# 8255_pio_1_4.net
KiCad netlist of a schematic drawn in EAGLE
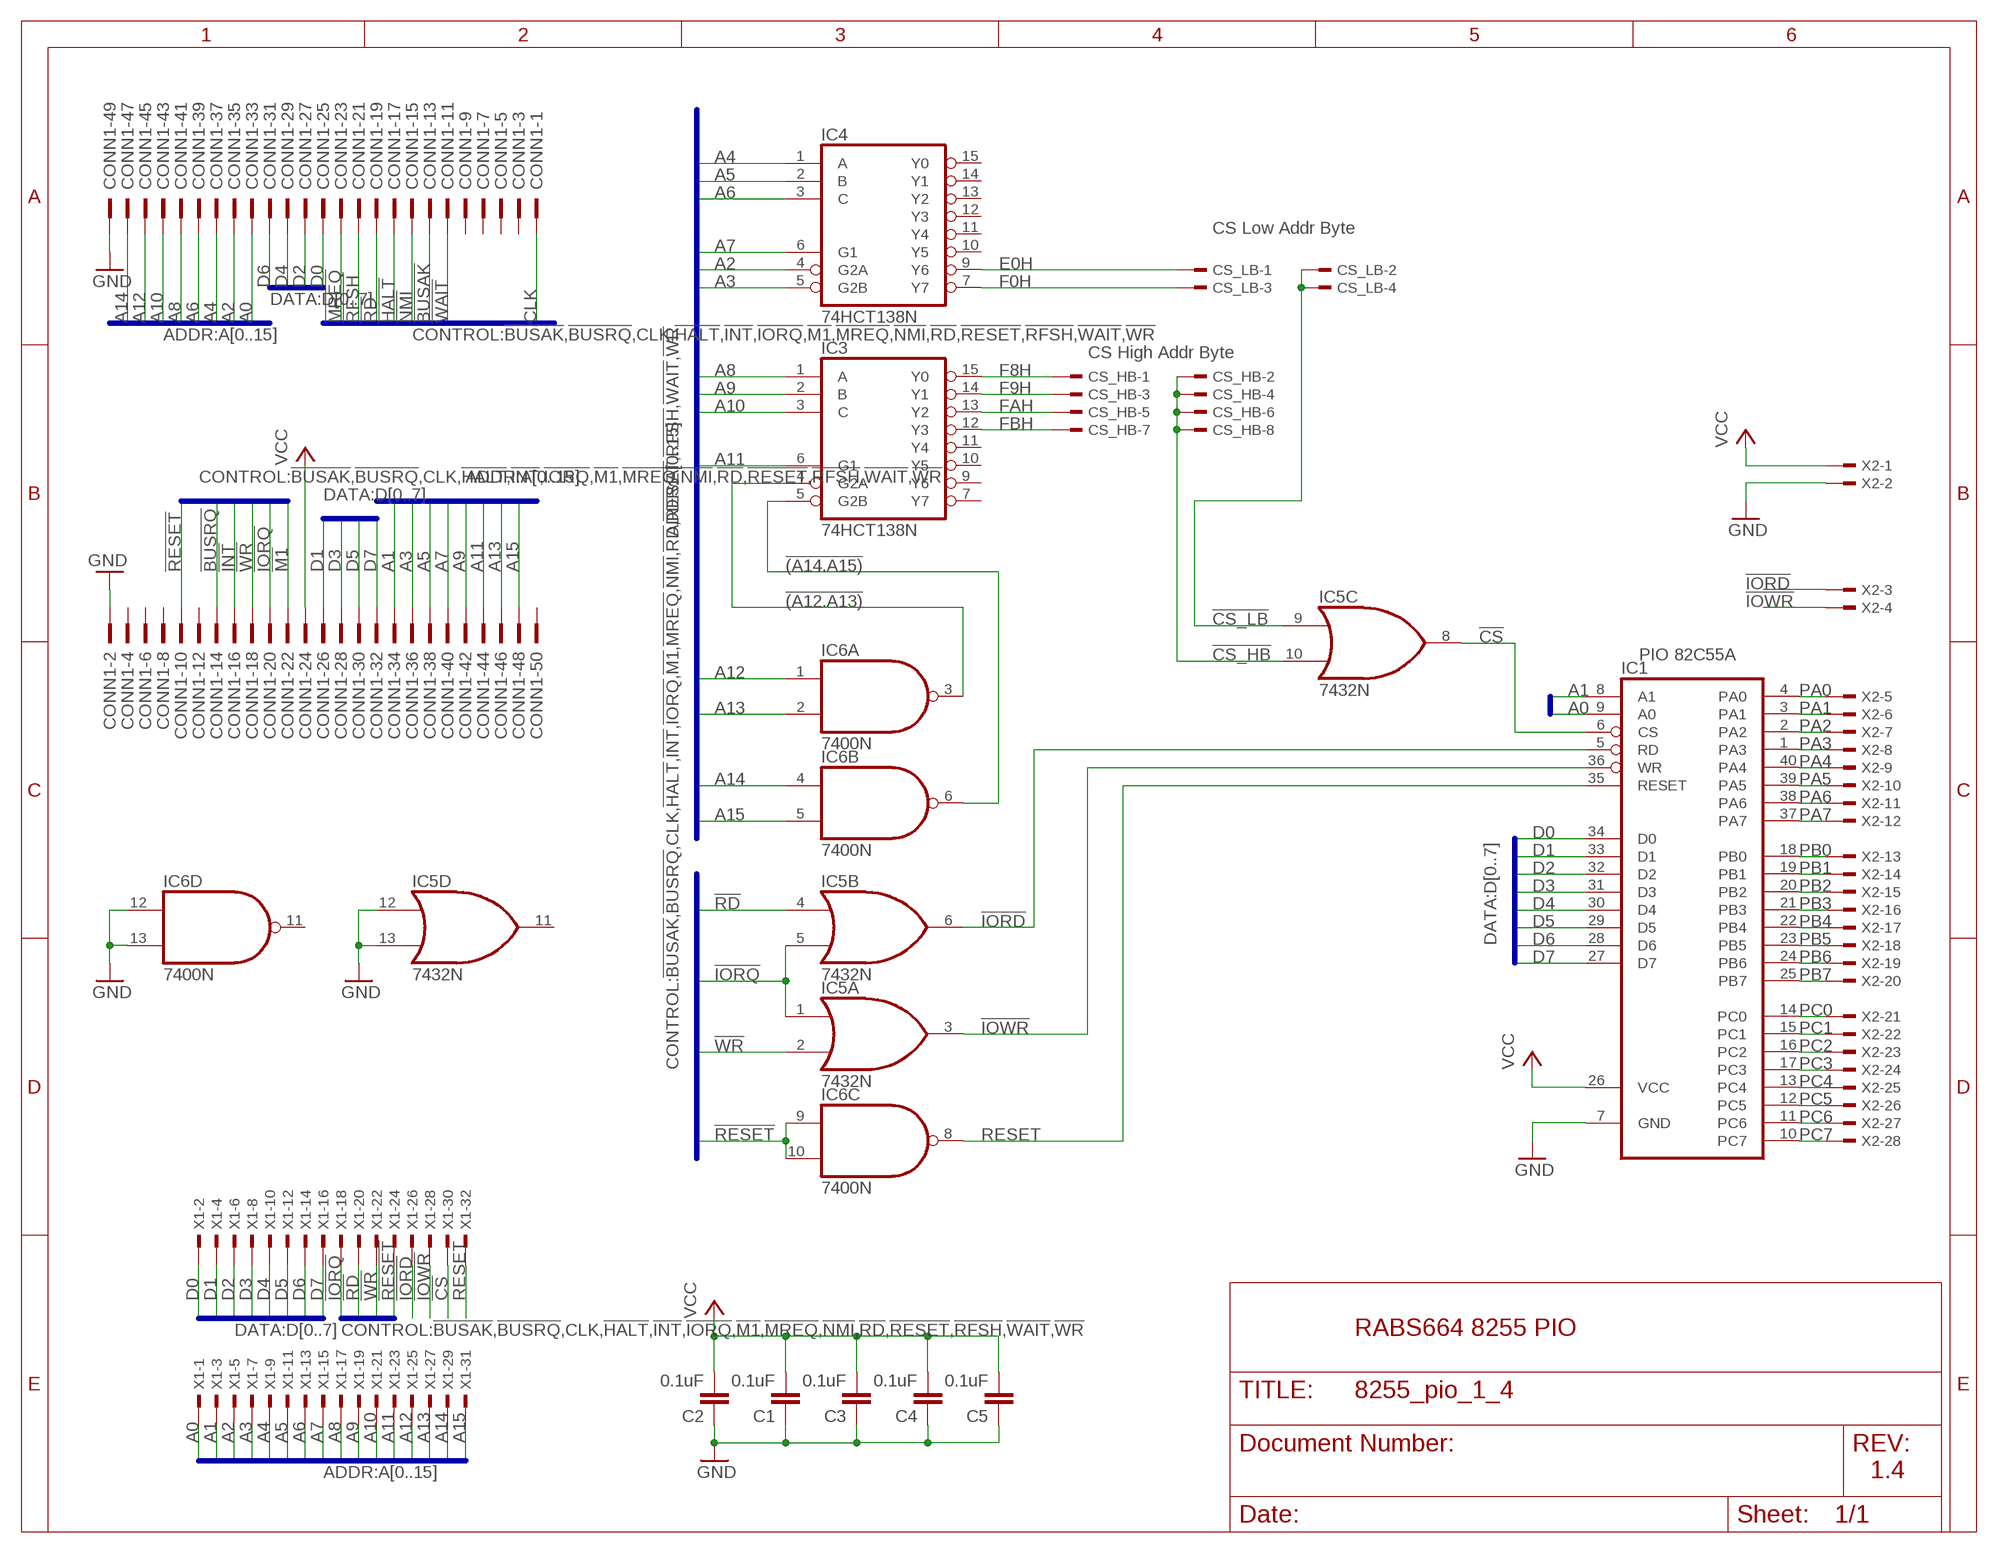
[diagram p0: schematic, sheet 1]

(export (version "E")
  (design (tool "Eeschema 10.0.6"))
  (components
    (comp (ref "C1")
      (value "0.1uF")
      (footprint "eagle-import:C050-025X075")
      (libsource (lib "eagle-import") (part "C-EU050-025X075"))
    )
    (comp (ref "C2")
      (value "0.1uF")
      (footprint "eagle-import:C050-025X075")
      (libsource (lib "eagle-import") (part "C-EU050-025X075"))
    )
    (comp (ref "C3")
      (value "0.1uF")
      (footprint "eagle-import:C050-025X075")
      (libsource (lib "eagle-import") (part "C-EU050-025X075"))
    )
    (comp (ref "C4")
      (value "0.1uF")
      (footprint "eagle-import:C050-025X075")
      (libsource (lib "eagle-import") (part "C-EU050-025X075"))
    )
    (comp (ref "C5")
      (value "0.1uF")
      (footprint "eagle-import:C050-025X075")
      (libsource (lib "eagle-import") (part "C-EU050-025X075"))
    )
    (comp (ref "CONN1")
      (value "2550-")
      (footprint "eagle-import:PAK100_2500-50")
      (fields (field (name "SPICEPREFIX") "X"))
      (libsource (lib "eagle-import") (part "2550-"))
    )
    (comp (ref "CS_HB")
      (value "TSW-104-07-G-D")
      (footprint "eagle-import:TSW-104-XX-G-D")
      (fields (field (name "MF") "Samtec Inc."))
      (libsource (lib "eagle-import") (part "TSW-104--G-D07"))
    )
    (comp (ref "CS_LB")
      (value "TSW-102-07-G-D")
      (footprint "eagle-import:TSW-102-XX-G-D")
      (fields (field (name "MF") "Samtec Inc."))
      (libsource (lib "eagle-import") (part "TSW-102--G-D07"))
    )
    (comp (ref "IC1")
      (value "82C55A")
      (footprint "eagle-import:DIL40")
      (fields (field (name "MF") "INTERSIL") (field (name "MPN") "IP82C55AZ"))
      (libsource (lib "eagle-import") (part "82C55A"))
    )
    (comp (ref "IC3")
      (value "74HCT138N")
      (footprint "eagle-import:DIL16")
      (libsource (lib "eagle-import") (part "74138NHCT"))
    )
    (comp (ref "IC4")
      (value "74HCT138N")
      (footprint "eagle-import:DIL16")
      (libsource (lib "eagle-import") (part "74138NHCT"))
    )
    (comp (ref "IC5")
      (value "7432N")
      (footprint "eagle-import:DIL14")
      (libsource (lib "eagle-import") (part "7432N"))
    )
    (comp (ref "IC6")
      (value "7400N")
      (footprint "eagle-import:DIL14")
      (libsource (lib "eagle-import") (part "7400N"))
    )
    (comp (ref "X1")
      (value "TSW-116-07-G-D")
      (footprint "eagle-import:TSW-116-XX-G-D")
      (fields (field (name "MF") "Samtec Inc."))
      (libsource (lib "eagle-import") (part "TSW-116--G-D07"))
    )
    (comp (ref "X2")
      (value "TSW-128-07-G-S")
      (footprint "eagle-import:TSW-128-XX-G-S")
      (fields (field (name "MF") "Samtec Inc."))
      (libsource (lib "eagle-import") (part "TSW-128--G-S07"))
    )
  )
  (nets
    (net (code "29") (name "A0") (class "Default")
      (node (ref "CONN1") (pin "33") (pinfunction "KL_33") (pintype "passive"))
      (node (ref "IC1") (pin "9") (pinfunction "A0_9") (pintype "input"))
      (node (ref "X1") (pin "1") (pinfunction "1_1") (pintype "passive"))
    )
    (net (code "30") (name "A1") (class "Default")
      (node (ref "CONN1") (pin "34") (pinfunction "KL_34") (pintype "passive"))
      (node (ref "IC1") (pin "8") (pinfunction "A1_8") (pintype "input"))
      (node (ref "X1") (pin "3") (pinfunction "1_3") (pintype "passive"))
    )
    (net (code "31") (name "A2") (class "Default")
      (node (ref "CONN1") (pin "35") (pinfunction "KL_35") (pintype "passive"))
      (node (ref "IC4") (pin "4") (pinfunction "G2A_4") (pintype "input"))
      (node (ref "X1") (pin "5") (pinfunction "1_5") (pintype "passive"))
    )
    (net (code "32") (name "A3") (class "Default")
      (node (ref "CONN1") (pin "36") (pinfunction "KL_36") (pintype "passive"))
      (node (ref "IC4") (pin "5") (pinfunction "G2B_5") (pintype "input"))
      (node (ref "X1") (pin "7") (pinfunction "1_7") (pintype "passive"))
    )
    (net (code "33") (name "A4") (class "Default")
      (node (ref "CONN1") (pin "37") (pinfunction "KL_37") (pintype "passive"))
      (node (ref "IC4") (pin "1") (pinfunction "A_1") (pintype "input"))
      (node (ref "X1") (pin "9") (pinfunction "1_9") (pintype "passive"))
    )
    (net (code "34") (name "A5") (class "Default")
      (node (ref "CONN1") (pin "38") (pinfunction "KL_38") (pintype "passive"))
      (node (ref "IC4") (pin "2") (pinfunction "B_2") (pintype "input"))
      (node (ref "X1") (pin "11") (pinfunction "1_11") (pintype "passive"))
    )
    (net (code "35") (name "A6") (class "Default")
      (node (ref "CONN1") (pin "39") (pinfunction "KL_39") (pintype "passive"))
      (node (ref "IC4") (pin "3") (pinfunction "C_3") (pintype "input"))
      (node (ref "X1") (pin "13") (pinfunction "1_13") (pintype "passive"))
    )
    (net (code "36") (name "A7") (class "Default")
      (node (ref "CONN1") (pin "40") (pinfunction "KL_40") (pintype "passive"))
      (node (ref "IC4") (pin "6") (pinfunction "G1_6") (pintype "input"))
      (node (ref "X1") (pin "15") (pinfunction "1_15") (pintype "passive"))
    )
    (net (code "37") (name "A8") (class "Default")
      (node (ref "CONN1") (pin "41") (pinfunction "KL_41") (pintype "passive"))
      (node (ref "IC3") (pin "1") (pinfunction "A_1") (pintype "input"))
      (node (ref "X1") (pin "17") (pinfunction "1_17") (pintype "passive"))
    )
    (net (code "38") (name "A9") (class "Default")
      (node (ref "CONN1") (pin "42") (pinfunction "KL_42") (pintype "passive"))
      (node (ref "IC3") (pin "2") (pinfunction "B_2") (pintype "input"))
      (node (ref "X1") (pin "19") (pinfunction "1_19") (pintype "passive"))
    )
    (net (code "39") (name "A10") (class "Default")
      (node (ref "CONN1") (pin "43") (pinfunction "KL_43") (pintype "passive"))
      (node (ref "IC3") (pin "3") (pinfunction "C_3") (pintype "input"))
      (node (ref "X1") (pin "21") (pinfunction "1_21") (pintype "passive"))
    )
    (net (code "40") (name "A11") (class "Default")
      (node (ref "CONN1") (pin "44") (pinfunction "KL_44") (pintype "passive"))
      (node (ref "IC3") (pin "6") (pinfunction "G1_6") (pintype "input"))
      (node (ref "X1") (pin "23") (pinfunction "1_23") (pintype "passive"))
    )
    (net (code "41") (name "A12") (class "Default")
      (node (ref "CONN1") (pin "45") (pinfunction "KL_45") (pintype "passive"))
      (node (ref "IC6") (pin "1") (pinfunction "I0_1") (pintype "input"))
      (node (ref "X1") (pin "25") (pinfunction "1_25") (pintype "passive"))
    )
    (net (code "42") (name "A13") (class "Default")
      (node (ref "CONN1") (pin "46") (pinfunction "KL_46") (pintype "passive"))
      (node (ref "IC6") (pin "2") (pinfunction "I1_2") (pintype "input"))
      (node (ref "X1") (pin "27") (pinfunction "1_27") (pintype "passive"))
    )
    (net (code "43") (name "A14") (class "Default")
      (node (ref "CONN1") (pin "47") (pinfunction "KL_47") (pintype "passive"))
      (node (ref "IC6") (pin "4") (pinfunction "I0_4") (pintype "input"))
      (node (ref "X1") (pin "29") (pinfunction "1_29") (pintype "passive"))
    )
    (net (code "44") (name "A15") (class "Default")
      (node (ref "CONN1") (pin "48") (pinfunction "KL_48") (pintype "passive"))
      (node (ref "IC6") (pin "5") (pinfunction "I1_5") (pintype "input"))
      (node (ref "X1") (pin "31") (pinfunction "1_31") (pintype "passive"))
    )
    (net (code "45") (name "CLK") (class "Default")
      (node (ref "CONN1") (pin "1") (pinfunction "KL_1") (pintype "passive"))
    )
    (net (code "46") (name "D0") (class "Default")
      (node (ref "CONN1") (pin "25") (pinfunction "KL_25") (pintype "passive"))
      (node (ref "IC1") (pin "34") (pinfunction "D0_34") (pintype "bidirectional"))
      (node (ref "X1") (pin "2") (pinfunction "1_2") (pintype "passive"))
    )
    (net (code "47") (name "D1") (class "Default")
      (node (ref "CONN1") (pin "26") (pinfunction "KL_26") (pintype "passive"))
      (node (ref "IC1") (pin "33") (pinfunction "D1_33") (pintype "bidirectional"))
      (node (ref "X1") (pin "4") (pinfunction "1_4") (pintype "passive"))
    )
    (net (code "48") (name "D2") (class "Default")
      (node (ref "CONN1") (pin "27") (pinfunction "KL_27") (pintype "passive"))
      (node (ref "IC1") (pin "32") (pinfunction "D2_32") (pintype "bidirectional"))
      (node (ref "X1") (pin "6") (pinfunction "1_6") (pintype "passive"))
    )
    (net (code "49") (name "D3") (class "Default")
      (node (ref "CONN1") (pin "28") (pinfunction "KL_28") (pintype "passive"))
      (node (ref "IC1") (pin "31") (pinfunction "D3_31") (pintype "bidirectional"))
      (node (ref "X1") (pin "8") (pinfunction "1_8") (pintype "passive"))
    )
    (net (code "50") (name "D4") (class "Default")
      (node (ref "CONN1") (pin "29") (pinfunction "KL_29") (pintype "passive"))
      (node (ref "IC1") (pin "30") (pinfunction "D4_30") (pintype "bidirectional"))
      (node (ref "X1") (pin "10") (pinfunction "1_10") (pintype "passive"))
    )
    (net (code "51") (name "D5") (class "Default")
      (node (ref "CONN1") (pin "30") (pinfunction "KL_30") (pintype "passive"))
      (node (ref "IC1") (pin "29") (pinfunction "D5_29") (pintype "bidirectional"))
      (node (ref "X1") (pin "12") (pinfunction "1_12") (pintype "passive"))
    )
    (net (code "52") (name "D6") (class "Default")
      (node (ref "CONN1") (pin "31") (pinfunction "KL_31") (pintype "passive"))
      (node (ref "IC1") (pin "28") (pinfunction "D6_28") (pintype "bidirectional"))
      (node (ref "X1") (pin "14") (pinfunction "1_14") (pintype "passive"))
    )
    (net (code "53") (name "D7") (class "Default")
      (node (ref "CONN1") (pin "32") (pinfunction "KL_32") (pintype "passive"))
      (node (ref "IC1") (pin "27") (pinfunction "D7_27") (pintype "bidirectional"))
      (node (ref "X1") (pin "16") (pinfunction "1_16") (pintype "passive"))
    )
    (net (code "54") (name "E0H") (class "Default")
      (node (ref "CS_LB") (pin "1") (pinfunction "1_1") (pintype "passive"))
      (node (ref "IC4") (pin "9") (pinfunction "Y6_9") (pintype "output"))
    )
    (net (code "55") (name "F0H") (class "Default")
      (node (ref "CS_LB") (pin "3") (pinfunction "1_3") (pintype "passive"))
      (node (ref "IC4") (pin "7") (pinfunction "Y7_7") (pintype "output"))
    )
    (net (code "56") (name "F8H") (class "Default")
      (node (ref "CS_HB") (pin "1") (pinfunction "1_1") (pintype "passive"))
      (node (ref "IC3") (pin "15") (pinfunction "Y0_15") (pintype "output"))
    )
    (net (code "57") (name "F9H") (class "Default")
      (node (ref "CS_HB") (pin "3") (pinfunction "1_3") (pintype "passive"))
      (node (ref "IC3") (pin "14") (pinfunction "Y1_14") (pintype "output"))
    )
    (net (code "58") (name "FAH") (class "Default")
      (node (ref "CS_HB") (pin "5") (pinfunction "1_5") (pintype "passive"))
      (node (ref "IC3") (pin "13") (pinfunction "Y2_13") (pintype "output"))
    )
    (net (code "59") (name "FBH") (class "Default")
      (node (ref "CS_HB") (pin "7") (pinfunction "1_7") (pintype "passive"))
      (node (ref "IC3") (pin "12") (pinfunction "Y3_12") (pintype "output"))
    )
    (net (code "60") (name "GND") (class "Default")
      (node (ref "C1") (pin "1") (pinfunction "1_1") (pintype "passive"))
      (node (ref "C2") (pin "1") (pinfunction "1_1") (pintype "passive"))
      (node (ref "C3") (pin "1") (pinfunction "1_1") (pintype "passive"))
      (node (ref "C4") (pin "1") (pinfunction "1_1") (pintype "passive"))
      (node (ref "C5") (pin "1") (pinfunction "1_1") (pintype "passive"))
      (node (ref "CONN1") (pin "2") (pinfunction "KL_2") (pintype "passive"))
      (node (ref "CONN1") (pin "49") (pinfunction "KL_49") (pintype "passive"))
      (node (ref "IC1") (pin "7") (pinfunction "GND_7") (pintype "power_in"))
      (node (ref "IC5") (pin "12") (pinfunction "I0_12") (pintype "input"))
      (node (ref "IC5") (pin "13") (pinfunction "I1_13") (pintype "input"))
      (node (ref "IC6") (pin "12") (pinfunction "I0_12") (pintype "input"))
      (node (ref "IC6") (pin "13") (pinfunction "I1_13") (pintype "input"))
      (node (ref "X2") (pin "2") (pinfunction "1_2") (pintype "passive"))
    )
    (net (code "61") (name "PA0") (class "Default")
      (node (ref "IC1") (pin "4") (pinfunction "PA0_4") (pintype "bidirectional"))
      (node (ref "X2") (pin "5") (pinfunction "1_5") (pintype "passive"))
    )
    (net (code "62") (name "PA1") (class "Default")
      (node (ref "IC1") (pin "3") (pinfunction "PA1_3") (pintype "bidirectional"))
      (node (ref "X2") (pin "6") (pinfunction "1_6") (pintype "passive"))
    )
    (net (code "63") (name "PA2") (class "Default")
      (node (ref "IC1") (pin "2") (pinfunction "PA2_2") (pintype "bidirectional"))
      (node (ref "X2") (pin "7") (pinfunction "1_7") (pintype "passive"))
    )
    (net (code "64") (name "PA3") (class "Default")
      (node (ref "IC1") (pin "1") (pinfunction "PA3_1") (pintype "bidirectional"))
      (node (ref "X2") (pin "8") (pinfunction "1_8") (pintype "passive"))
    )
    (net (code "65") (name "PA4") (class "Default")
      (node (ref "IC1") (pin "40") (pinfunction "PA4_40") (pintype "bidirectional"))
      (node (ref "X2") (pin "9") (pinfunction "1_9") (pintype "passive"))
    )
    (net (code "66") (name "PA5") (class "Default")
      (node (ref "IC1") (pin "39") (pinfunction "PA5_39") (pintype "bidirectional"))
      (node (ref "X2") (pin "10") (pinfunction "1_10") (pintype "passive"))
    )
    (net (code "67") (name "PA6") (class "Default")
      (node (ref "IC1") (pin "38") (pinfunction "PA6_38") (pintype "bidirectional"))
      (node (ref "X2") (pin "11") (pinfunction "1_11") (pintype "passive"))
    )
    (net (code "68") (name "PA7") (class "Default")
      (node (ref "IC1") (pin "37") (pinfunction "PA7_37") (pintype "bidirectional"))
      (node (ref "X2") (pin "12") (pinfunction "1_12") (pintype "passive"))
    )
    (net (code "69") (name "PB0") (class "Default")
      (node (ref "IC1") (pin "18") (pinfunction "PB0_18") (pintype "bidirectional"))
      (node (ref "X2") (pin "13") (pinfunction "1_13") (pintype "passive"))
    )
    (net (code "70") (name "PB1") (class "Default")
      (node (ref "IC1") (pin "19") (pinfunction "PB1_19") (pintype "bidirectional"))
      (node (ref "X2") (pin "14") (pinfunction "1_14") (pintype "passive"))
    )
    (net (code "71") (name "PB2") (class "Default")
      (node (ref "IC1") (pin "20") (pinfunction "PB2_20") (pintype "bidirectional"))
      (node (ref "X2") (pin "15") (pinfunction "1_15") (pintype "passive"))
    )
    (net (code "72") (name "PB3") (class "Default")
      (node (ref "IC1") (pin "21") (pinfunction "PB3_21") (pintype "bidirectional"))
      (node (ref "X2") (pin "16") (pinfunction "1_16") (pintype "passive"))
    )
    (net (code "73") (name "PB4") (class "Default")
      (node (ref "IC1") (pin "22") (pinfunction "PB4_22") (pintype "bidirectional"))
      (node (ref "X2") (pin "17") (pinfunction "1_17") (pintype "passive"))
    )
    (net (code "74") (name "PB5") (class "Default")
      (node (ref "IC1") (pin "23") (pinfunction "PB5_23") (pintype "bidirectional"))
      (node (ref "X2") (pin "18") (pinfunction "1_18") (pintype "passive"))
    )
    (net (code "75") (name "PB6") (class "Default")
      (node (ref "IC1") (pin "24") (pinfunction "PB6_24") (pintype "bidirectional"))
      (node (ref "X2") (pin "19") (pinfunction "1_19") (pintype "passive"))
    )
    (net (code "76") (name "PB7") (class "Default")
      (node (ref "IC1") (pin "25") (pinfunction "PB7_25") (pintype "bidirectional"))
      (node (ref "X2") (pin "20") (pinfunction "1_20") (pintype "passive"))
    )
    (net (code "77") (name "PC0") (class "Default")
      (node (ref "IC1") (pin "14") (pinfunction "PC0_14") (pintype "bidirectional"))
      (node (ref "X2") (pin "21") (pinfunction "1_21") (pintype "passive"))
    )
    (net (code "78") (name "PC1") (class "Default")
      (node (ref "IC1") (pin "15") (pinfunction "PC1_15") (pintype "bidirectional"))
      (node (ref "X2") (pin "22") (pinfunction "1_22") (pintype "passive"))
    )
    (net (code "79") (name "PC2") (class "Default")
      (node (ref "IC1") (pin "16") (pinfunction "PC2_16") (pintype "bidirectional"))
      (node (ref "X2") (pin "23") (pinfunction "1_23") (pintype "passive"))
    )
    (net (code "80") (name "PC3") (class "Default")
      (node (ref "IC1") (pin "17") (pinfunction "PC3_17") (pintype "bidirectional"))
      (node (ref "X2") (pin "24") (pinfunction "1_24") (pintype "passive"))
    )
    (net (code "81") (name "PC4") (class "Default")
      (node (ref "IC1") (pin "13") (pinfunction "PC4_13") (pintype "bidirectional"))
      (node (ref "X2") (pin "25") (pinfunction "1_25") (pintype "passive"))
    )
    (net (code "82") (name "PC5") (class "Default")
      (node (ref "IC1") (pin "12") (pinfunction "PC5_12") (pintype "bidirectional"))
      (node (ref "X2") (pin "26") (pinfunction "1_26") (pintype "passive"))
    )
    (net (code "83") (name "PC6") (class "Default")
      (node (ref "IC1") (pin "11") (pinfunction "PC6_11") (pintype "bidirectional"))
      (node (ref "X2") (pin "27") (pinfunction "1_27") (pintype "passive"))
    )
    (net (code "84") (name "PC7") (class "Default")
      (node (ref "IC1") (pin "10") (pinfunction "PC7_10") (pintype "bidirectional"))
      (node (ref "X2") (pin "28") (pinfunction "1_28") (pintype "passive"))
    )
    (net (code "85") (name "RESET") (class "Default")
      (node (ref "IC1") (pin "35") (pinfunction "RESET_35") (pintype "input"))
      (node (ref "IC6") (pin "8") (pinfunction "O_8") (pintype "output"))
      (node (ref "X1") (pin "32") (pinfunction "1_32") (pintype "passive"))
    )
    (net (code "86") (name "VCC") (class "Default")
      (node (ref "C1") (pin "2") (pinfunction "2_2") (pintype "passive"))
      (node (ref "C2") (pin "2") (pinfunction "2_2") (pintype "passive"))
      (node (ref "C3") (pin "2") (pinfunction "2_2") (pintype "passive"))
      (node (ref "C4") (pin "2") (pinfunction "2_2") (pintype "passive"))
      (node (ref "C5") (pin "2") (pinfunction "2_2") (pintype "passive"))
      (node (ref "CONN1") (pin "24") (pinfunction "KL_24") (pintype "passive"))
      (node (ref "IC1") (pin "26") (pinfunction "VCC_26") (pintype "power_in"))
      (node (ref "X2") (pin "1") (pinfunction "1_1") (pintype "passive"))
    )
    (net (code "87") (name "unconnected-(CONN1AH-KL-Pad4)") (class "Default")
      (node (ref "CONN1") (pin "4") (pinfunction "KL_4") (pintype "passive"))
    )
    (net (code "88") (name "unconnected-(CONN1AS-KL-Pad5)") (class "Default")
      (node (ref "CONN1") (pin "5") (pinfunction "KL_5") (pintype "passive"))
    )
    (net (code "89") (name "unconnected-(CONN1AT-KL-Pad50)") (class "Default")
      (node (ref "CONN1") (pin "50") (pinfunction "KL_50") (pintype "passive"))
    )
    (net (code "90") (name "unconnected-(CONN1AU-KL-Pad6)") (class "Default")
      (node (ref "CONN1") (pin "6") (pinfunction "KL_6") (pintype "passive"))
    )
    (net (code "91") (name "unconnected-(CONN1AV-KL-Pad7)") (class "Default")
      (node (ref "CONN1") (pin "7") (pinfunction "KL_7") (pintype "passive"))
    )
    (net (code "92") (name "unconnected-(CONN1AW-KL-Pad8)") (class "Default")
      (node (ref "CONN1") (pin "8") (pinfunction "KL_8") (pintype "passive"))
    )
    (net (code "93") (name "unconnected-(CONN1AX-KL-Pad9)") (class "Default")
      (node (ref "CONN1") (pin "9") (pinfunction "KL_9") (pintype "passive"))
    )
    (net (code "94") (name "unconnected-(CONN1D-KL-Pad12)") (class "Default")
      (node (ref "CONN1") (pin "12") (pinfunction "KL_12") (pintype "passive"))
    )
    (net (code "95") (name "unconnected-(CONN1W-KL-Pad3)") (class "Default")
      (node (ref "CONN1") (pin "3") (pinfunction "KL_3") (pintype "passive"))
    )
    (net (code "96") (name "unconnected-(IC3A-Y4-Pad11)") (class "Default")
      (node (ref "IC3") (pin "11") (pinfunction "Y4_11") (pintype "output"))
    )
    (net (code "97") (name "unconnected-(IC3A-Y5-Pad10)") (class "Default")
      (node (ref "IC3") (pin "10") (pinfunction "Y5_10") (pintype "output"))
    )
    (net (code "98") (name "unconnected-(IC3A-Y6-Pad9)") (class "Default")
      (node (ref "IC3") (pin "9") (pinfunction "Y6_9") (pintype "output"))
    )
    (net (code "99") (name "unconnected-(IC3A-Y7-Pad7)") (class "Default")
      (node (ref "IC3") (pin "7") (pinfunction "Y7_7") (pintype "output"))
    )
    (net (code "100") (name "unconnected-(IC4A-Y0-Pad15)") (class "Default")
      (node (ref "IC4") (pin "15") (pinfunction "Y0_15") (pintype "output"))
    )
    (net (code "101") (name "unconnected-(IC4A-Y1-Pad14)") (class "Default")
      (node (ref "IC4") (pin "14") (pinfunction "Y1_14") (pintype "output"))
    )
    (net (code "102") (name "unconnected-(IC4A-Y2-Pad13)") (class "Default")
      (node (ref "IC4") (pin "13") (pinfunction "Y2_13") (pintype "output"))
    )
    (net (code "103") (name "unconnected-(IC4A-Y3-Pad12)") (class "Default")
      (node (ref "IC4") (pin "12") (pinfunction "Y3_12") (pintype "output"))
    )
    (net (code "104") (name "unconnected-(IC4A-Y4-Pad11)") (class "Default")
      (node (ref "IC4") (pin "11") (pinfunction "Y4_11") (pintype "output"))
    )
    (net (code "105") (name "unconnected-(IC4A-Y5-Pad10)") (class "Default")
      (node (ref "IC4") (pin "10") (pinfunction "Y5_10") (pintype "output"))
    )
    (net (code "106") (name "unconnected-(IC5D-O-Pad11)") (class "Default")
      (node (ref "IC5") (pin "11") (pinfunction "O_11") (pintype "output"))
    )
    (net (code "107") (name "unconnected-(IC6D-O-Pad11)") (class "Default")
      (node (ref "IC6") (pin "11") (pinfunction "O_11") (pintype "output"))
    )
    (net (code "108") (name "~{(A12.A13})") (class "Default")
      (node (ref "IC3") (pin "4") (pinfunction "G2A_4") (pintype "input"))
      (node (ref "IC6") (pin "3") (pinfunction "O_3") (pintype "output"))
    )
    (net (code "109") (name "~{(A14.A15})") (class "Default")
      (node (ref "IC3") (pin "5") (pinfunction "G2B_5") (pintype "input"))
      (node (ref "IC6") (pin "6") (pinfunction "O_6") (pintype "output"))
    )
    (net (code "110") (name "~{BUSAK}") (class "Default")
      (node (ref "CONN1") (pin "13") (pinfunction "KL_13") (pintype "passive"))
    )
    (net (code "111") (name "~{BUSRQ}") (class "Default")
      (node (ref "CONN1") (pin "14") (pinfunction "KL_14") (pintype "passive"))
    )
    (net (code "112") (name "~{CS_HB}") (class "Default")
      (node (ref "CS_HB") (pin "2") (pinfunction "1_2") (pintype "passive"))
      (node (ref "CS_HB") (pin "4") (pinfunction "1_4") (pintype "passive"))
      (node (ref "CS_HB") (pin "6") (pinfunction "1_6") (pintype "passive"))
      (node (ref "CS_HB") (pin "8") (pinfunction "1_8") (pintype "passive"))
      (node (ref "IC5") (pin "10") (pinfunction "I1_10") (pintype "input"))
    )
    (net (code "113") (name "~{CS_LB}") (class "Default")
      (node (ref "CS_LB") (pin "2") (pinfunction "1_2") (pintype "passive"))
      (node (ref "CS_LB") (pin "4") (pinfunction "1_4") (pintype "passive"))
      (node (ref "IC5") (pin "9") (pinfunction "I0_9") (pintype "input"))
    )
    (net (code "114") (name "~{CS}") (class "Default")
      (node (ref "IC1") (pin "6") (pinfunction "CS_6") (pintype "input"))
      (node (ref "IC5") (pin "8") (pinfunction "O_8") (pintype "output"))
      (node (ref "X1") (pin "30") (pinfunction "1_30") (pintype "passive"))
    )
    (net (code "115") (name "~{HALT}") (class "Default")
      (node (ref "CONN1") (pin "17") (pinfunction "KL_17") (pintype "passive"))
    )
    (net (code "116") (name "~{INT}") (class "Default")
      (node (ref "CONN1") (pin "16") (pinfunction "KL_16") (pintype "passive"))
    )
    (net (code "117") (name "~{IORD}") (class "Default")
      (node (ref "IC1") (pin "5") (pinfunction "RD_5") (pintype "input"))
      (node (ref "IC5") (pin "6") (pinfunction "O_6") (pintype "output"))
      (node (ref "X1") (pin "26") (pinfunction "1_26") (pintype "passive"))
      (node (ref "X2") (pin "3") (pinfunction "1_3") (pintype "passive"))
    )
    (net (code "118") (name "~{IORQ}") (class "Default")
      (node (ref "CONN1") (pin "20") (pinfunction "KL_20") (pintype "passive"))
      (node (ref "IC5") (pin "1") (pinfunction "I0_1") (pintype "input"))
      (node (ref "IC5") (pin "5") (pinfunction "I1_5") (pintype "input"))
      (node (ref "X1") (pin "18") (pinfunction "1_18") (pintype "passive"))
    )
    (net (code "119") (name "~{IOWR}") (class "Default")
      (node (ref "IC1") (pin "36") (pinfunction "WR_36") (pintype "input"))
      (node (ref "IC5") (pin "3") (pinfunction "O_3") (pintype "output"))
      (node (ref "X1") (pin "28") (pinfunction "1_28") (pintype "passive"))
      (node (ref "X2") (pin "4") (pinfunction "1_4") (pintype "passive"))
    )
    (net (code "120") (name "~{M1}") (class "Default")
      (node (ref "CONN1") (pin "22") (pinfunction "KL_22") (pintype "passive"))
    )
    (net (code "121") (name "~{MREQ}") (class "Default")
      (node (ref "CONN1") (pin "23") (pinfunction "KL_23") (pintype "passive"))
    )
    (net (code "122") (name "~{NMI}") (class "Default")
      (node (ref "CONN1") (pin "15") (pinfunction "KL_15") (pintype "passive"))
    )
    (net (code "123") (name "~{RD}") (class "Default")
      (node (ref "CONN1") (pin "19") (pinfunction "KL_19") (pintype "passive"))
      (node (ref "IC5") (pin "4") (pinfunction "I0_4") (pintype "input"))
      (node (ref "X1") (pin "20") (pinfunction "1_20") (pintype "passive"))
    )
    (net (code "124") (name "~{RESET}") (class "Default")
      (node (ref "CONN1") (pin "10") (pinfunction "KL_10") (pintype "passive"))
      (node (ref "IC6") (pin "10") (pinfunction "I1_10") (pintype "input"))
      (node (ref "IC6") (pin "9") (pinfunction "I0_9") (pintype "input"))
      (node (ref "X1") (pin "24") (pinfunction "1_24") (pintype "passive"))
    )
    (net (code "125") (name "~{RFSH}") (class "Default")
      (node (ref "CONN1") (pin "21") (pinfunction "KL_21") (pintype "passive"))
    )
    (net (code "126") (name "~{WAIT}") (class "Default")
      (node (ref "CONN1") (pin "11") (pinfunction "KL_11") (pintype "passive"))
    )
    (net (code "127") (name "~{WR}") (class "Default")
      (node (ref "CONN1") (pin "18") (pinfunction "KL_18") (pintype "passive"))
      (node (ref "IC5") (pin "2") (pinfunction "I1_2") (pintype "input"))
      (node (ref "X1") (pin "22") (pinfunction "1_22") (pintype "passive"))
    )
  )
)
